# SignBuddy_Main_Board_Schematic.net
KiCad netlist of a schematic drawn in EAGLE
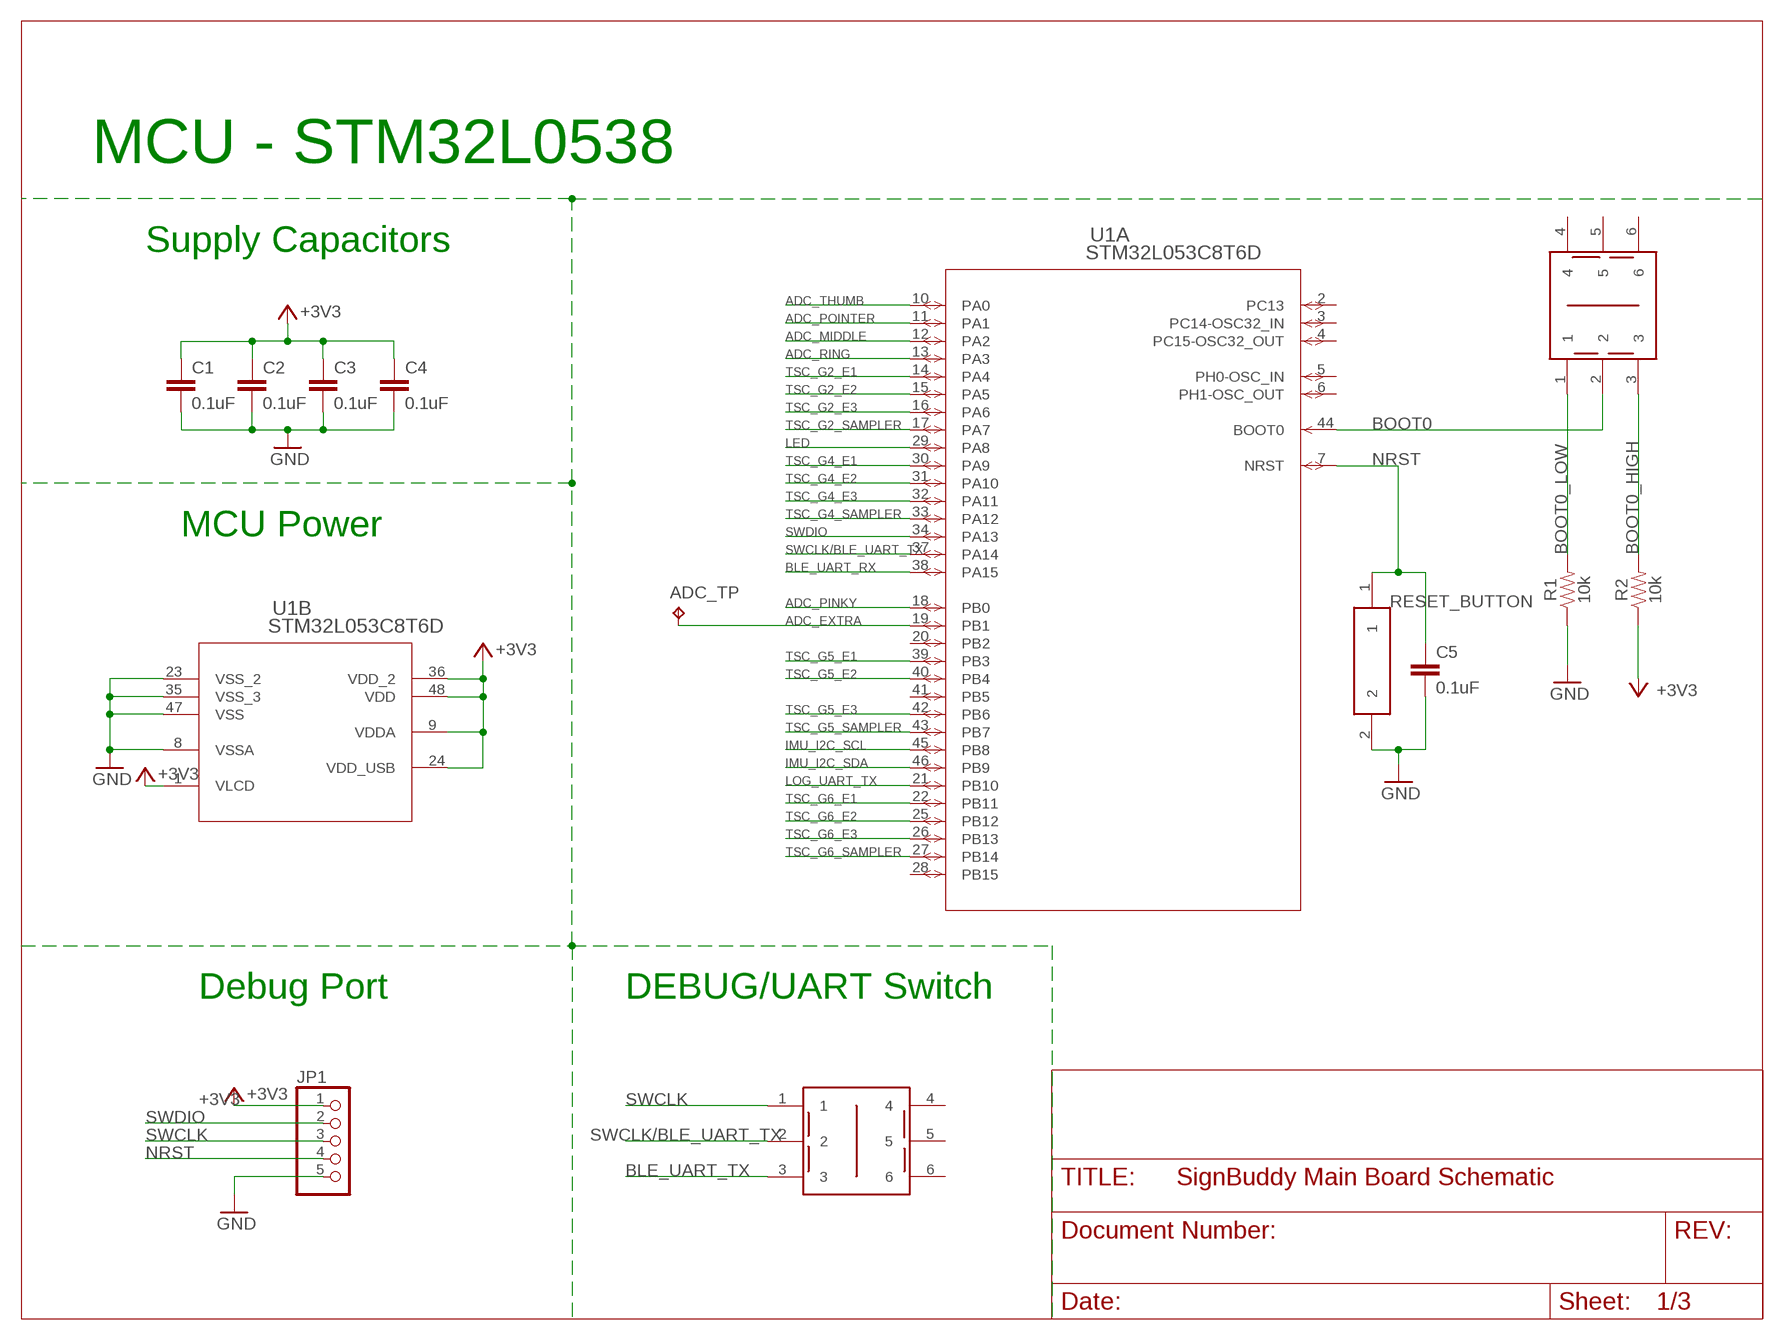
[diagram p0: schematic, sheet 1]
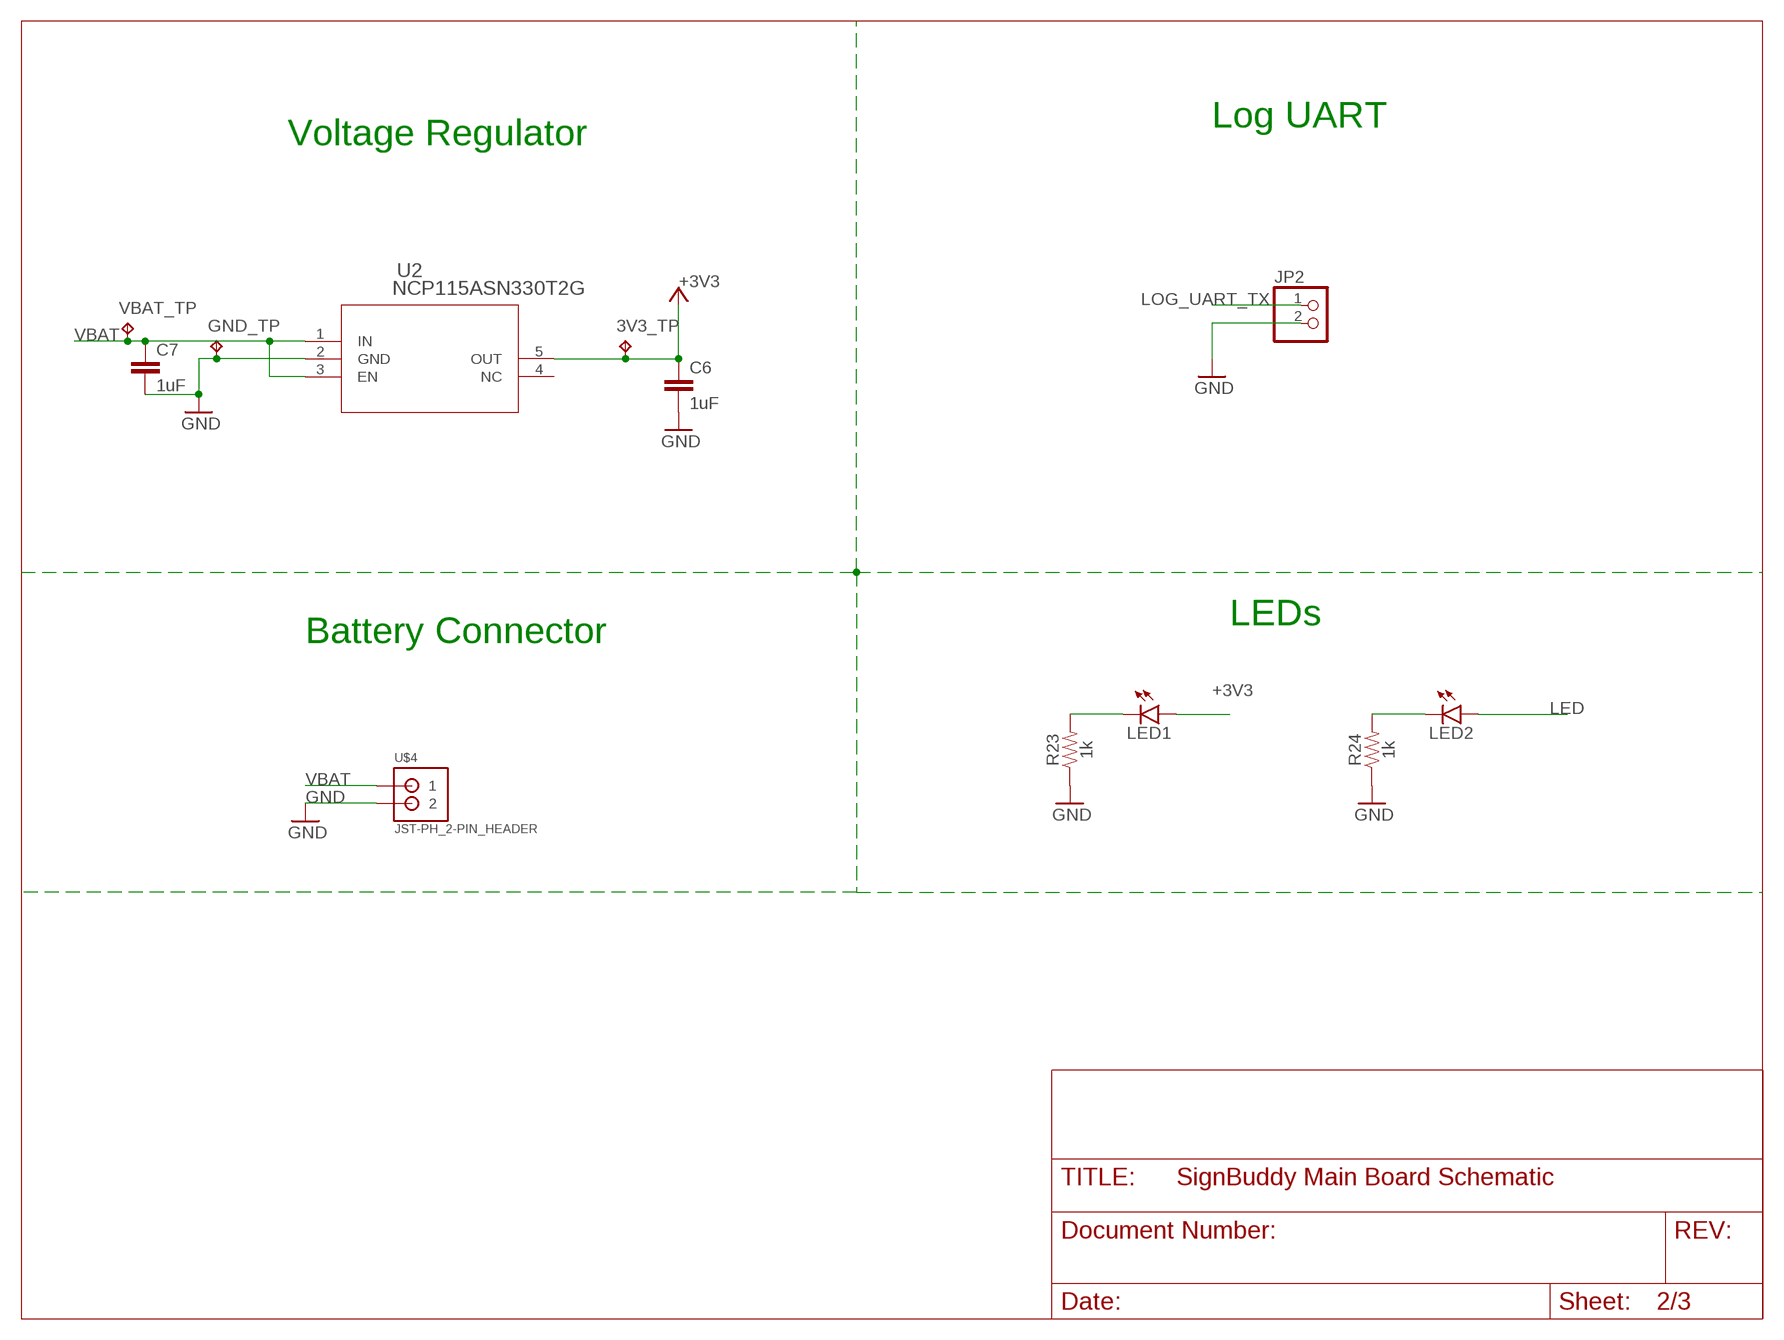
[diagram p1: schematic, sheet 2]
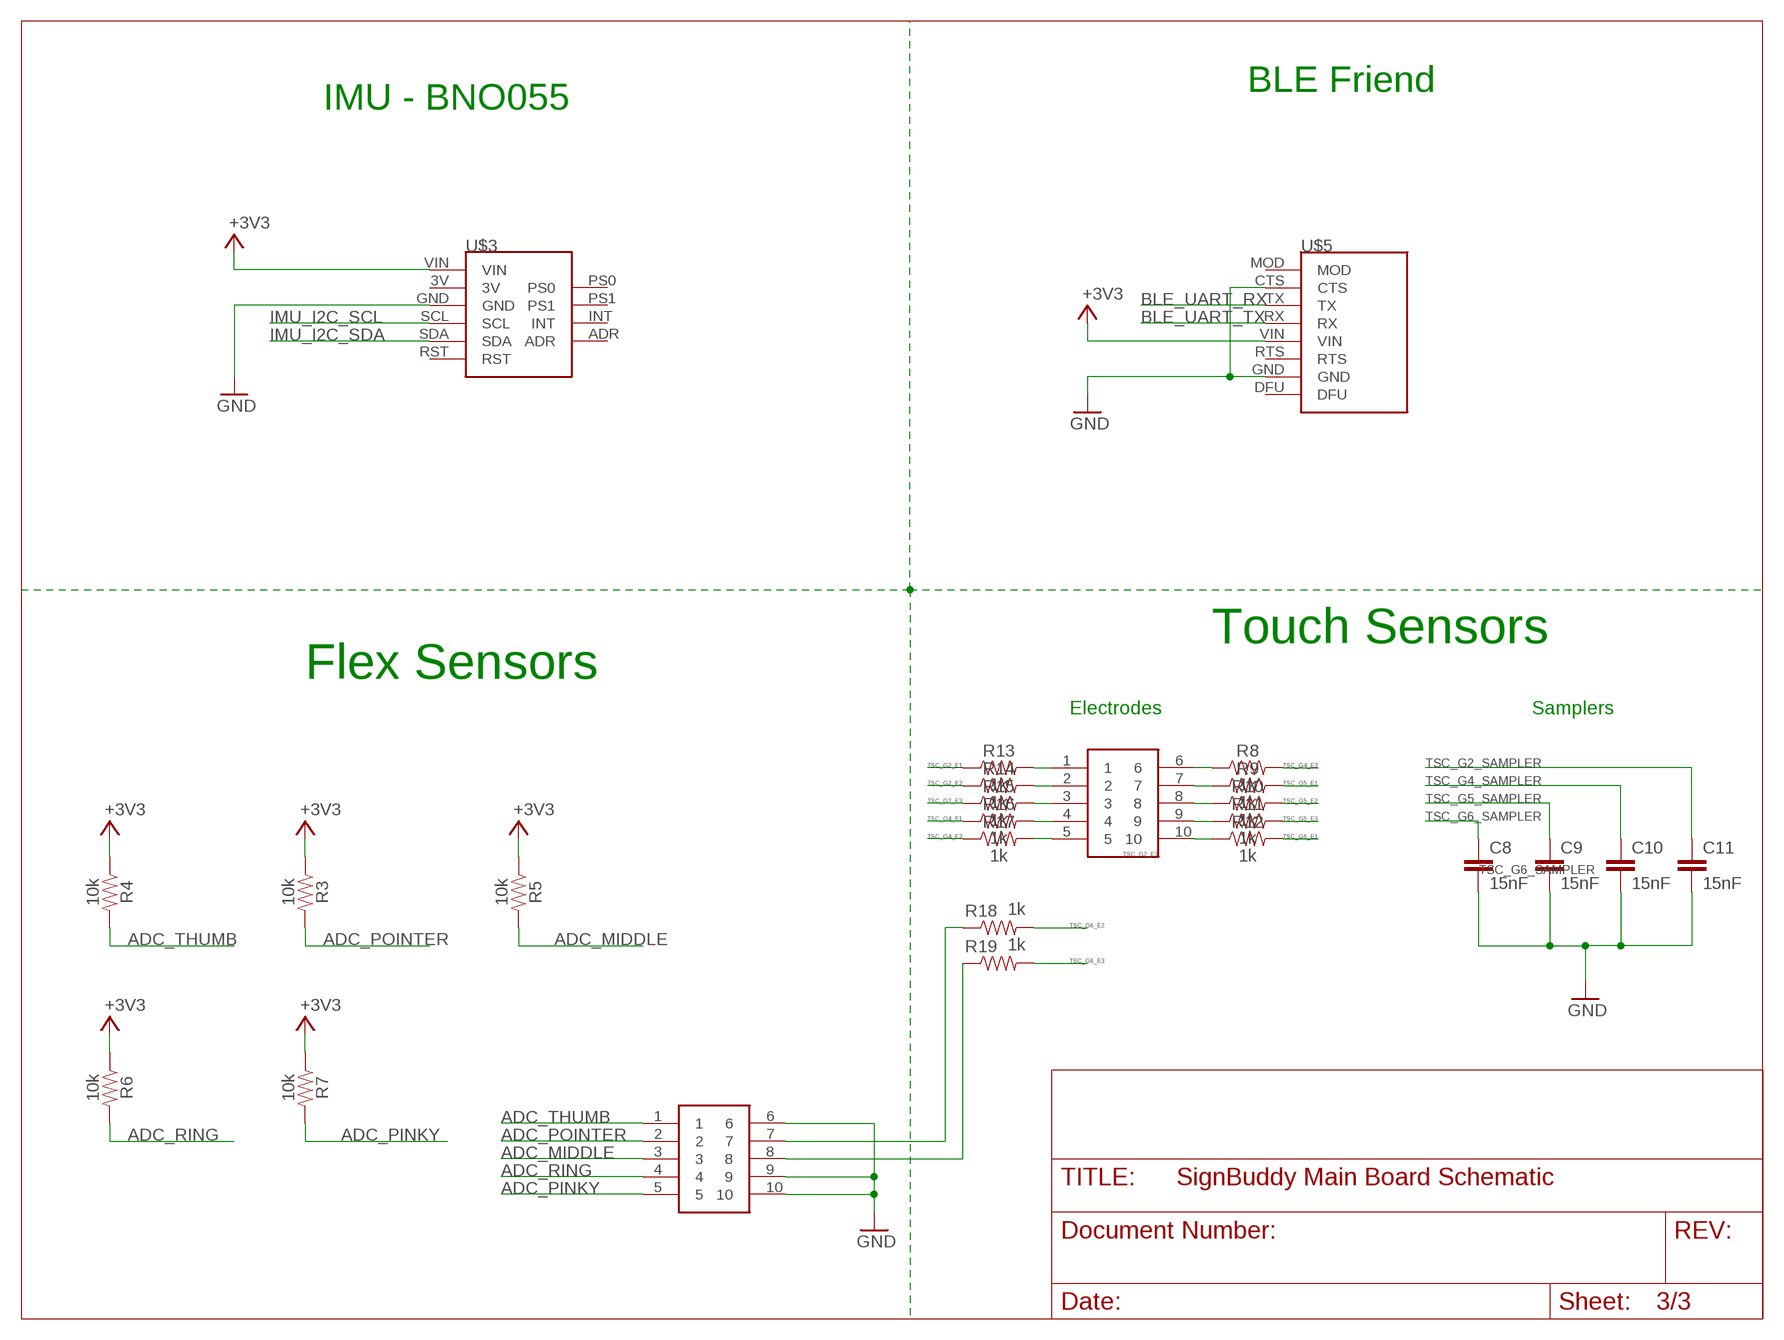
[diagram p2: schematic, sheet 3]

(export (version "E")
  (design (tool "Eeschema 10.0.6"))
  (components
    (comp (ref "ADC_TP")
      (value "TPB1,27")
      (footprint "eagle-import:B1,27")
      (libsource (lib "eagle-import") (part "TPB1,27"))
    )
    (comp (ref "C1")
      (value "0.1uF")
      (footprint "eagle-import:0603")
      (libsource (lib "eagle-import") (part "10UF-0603-6.3V-20%"))
    )
    (comp (ref "C2")
      (value "0.1uF")
      (footprint "eagle-import:0603")
      (libsource (lib "eagle-import") (part "10UF-0603-6.3V-20%"))
    )
    (comp (ref "C3")
      (value "0.1uF")
      (footprint "eagle-import:0603")
      (libsource (lib "eagle-import") (part "10UF-0603-6.3V-20%"))
    )
    (comp (ref "C4")
      (value "0.1uF")
      (footprint "eagle-import:0603")
      (libsource (lib "eagle-import") (part "10UF-0603-6.3V-20%"))
    )
    (comp (ref "C5")
      (value "0.1uF")
      (footprint "eagle-import:0603")
      (libsource (lib "eagle-import") (part "10UF-0603-6.3V-20%"))
    )
    (comp (ref "JP1")
      (value "PINHD-1X5")
      (footprint "eagle-import:1X05")
      (libsource (lib "eagle-import") (part "PINHD-1X5"))
    )
    (comp (ref "R1")
      (value "10k")
      (footprint "eagle-import:0603")
      (libsource (lib "eagle-import") (part "1.8KOHM-0603-1/10W-1%"))
    )
    (comp (ref "R2")
      (value "10k")
      (footprint "eagle-import:0603")
      (libsource (lib "eagle-import") (part "1.8KOHM-0603-1/10W-1%"))
    )
    (comp (ref "RESET_BUTTON")
      (value "PUSH_BUTTON")
      (footprint "eagle-import:PUSH_BUTTON")
      (libsource (lib "eagle-import") (part "PUSH_BUTTON"))
    )
    (comp (ref "U$1")
      (value "SLIDE_SWITCH")
      (footprint "eagle-import:SLIDE_SWITCH")
      (libsource (lib "eagle-import") (part "SLIDE_SWITCH"))
    )
    (comp (ref "U$2")
      (value "SLIDE_SWITCH")
      (footprint "eagle-import:SLIDE_SWITCH")
      (libsource (lib "eagle-import") (part "SLIDE_SWITCH"))
    )
    (comp (ref "U1")
      (value "STM32L053C8T6D")
      (footprint "eagle-import:LQFP48-7X7MM")
      (fields (field (name "COPYRIGHT") "Copyright (C) 2022 Ultra Librarian. All rights reserved."))
      (libsource (lib "eagle-import") (part "STM32L053C8T6D"))
    )
    (comp (ref "3V3_TP")
      (value "TPB1,27")
      (footprint "eagle-import:B1,27")
      (libsource (lib "eagle-import") (part "TPB1,27"))
    )
    (comp (ref "C6")
      (value "1uF")
      (footprint "eagle-import:0603")
      (libsource (lib "eagle-import") (part "10UF-0603-6.3V-20%"))
    )
    (comp (ref "C7")
      (value "1uF")
      (footprint "eagle-import:0603")
      (libsource (lib "eagle-import") (part "10UF-0603-6.3V-20%"))
    )
    (comp (ref "GND_TP")
      (value "TPB1,27")
      (footprint "eagle-import:B1,27")
      (libsource (lib "eagle-import") (part "TPB1,27"))
    )
    (comp (ref "JP2")
      (value "PINHD-1X2")
      (footprint "eagle-import:1X02")
      (libsource (lib "eagle-import") (part "PINHD-1X2"))
    )
    (comp (ref "LED1")
      (value "LEDCHIP-LED0603")
      (footprint "eagle-import:CHIP-LED0603")
      (libsource (lib "eagle-import") (part "LEDCHIP-LED0603"))
    )
    (comp (ref "LED2")
      (value "LEDCHIP-LED0603")
      (footprint "eagle-import:CHIP-LED0603")
      (libsource (lib "eagle-import") (part "LEDCHIP-LED0603"))
    )
    (comp (ref "R23")
      (value "1k")
      (footprint "eagle-import:0603")
      (libsource (lib "eagle-import") (part "1.5KOHM-0603-1/10W-1%"))
    )
    (comp (ref "R24")
      (value "1k")
      (footprint "eagle-import:0603")
      (libsource (lib "eagle-import") (part "1.5KOHM-0603-1/10W-1%"))
    )
    (comp (ref "U$4")
      (value "JST-PH_2-PIN_HEADER")
      (footprint "eagle-import:JST_B2B-PH_HEADER")
      (libsource (lib "eagle-import") (part "JST-PH_2-PIN_HEADER"))
    )
    (comp (ref "U2")
      (value "NCP115ASN330T2G")
      (footprint "eagle-import:TSOP-5-483-N_ONS")
      (fields (field (name "COPYRIGHT") "Copyright (C) 2022 Ultra Librarian. All rights reserved."))
      (libsource (lib "eagle-import") (part "NCP115ASN330T2G"))
    )
    (comp (ref "VBAT_TP")
      (value "TPB1,27")
      (footprint "eagle-import:B1,27")
      (libsource (lib "eagle-import") (part "TPB1,27"))
    )
    (comp (ref "C8")
      (value "15nF")
      (footprint "eagle-import:0603")
      (libsource (lib "eagle-import") (part "10UF-0603-6.3V-20%"))
    )
    (comp (ref "C9")
      (value "15nF")
      (footprint "eagle-import:0603")
      (libsource (lib "eagle-import") (part "10UF-0603-6.3V-20%"))
    )
    (comp (ref "C10")
      (value "15nF")
      (footprint "eagle-import:0603")
      (libsource (lib "eagle-import") (part "10UF-0603-6.3V-20%"))
    )
    (comp (ref "C11")
      (value "15nF")
      (footprint "eagle-import:0603")
      (libsource (lib "eagle-import") (part "10UF-0603-6.3V-20%"))
    )
    (comp (ref "R3")
      (value "10k")
      (footprint "eagle-import:0603")
      (libsource (lib "eagle-import") (part "10KOHM-0603-1/10W-1%"))
    )
    (comp (ref "R4")
      (value "10k")
      (footprint "eagle-import:0603")
      (libsource (lib "eagle-import") (part "10KOHM-0603-1/10W-1%"))
    )
    (comp (ref "R5")
      (value "10k")
      (footprint "eagle-import:0603")
      (libsource (lib "eagle-import") (part "10KOHM-0603-1/10W-1%"))
    )
    (comp (ref "R6")
      (value "10k")
      (footprint "eagle-import:0603")
      (libsource (lib "eagle-import") (part "10KOHM-0603-1/10W-1%"))
    )
    (comp (ref "R7")
      (value "10k")
      (footprint "eagle-import:0603")
      (libsource (lib "eagle-import") (part "10KOHM-0603-1/10W-1%"))
    )
    (comp (ref "R8")
      (value "1k")
      (footprint "eagle-import:0603")
      (libsource (lib "eagle-import") (part "10KOHM-0603-1/10W-1%"))
    )
    (comp (ref "R9")
      (value "1k")
      (footprint "eagle-import:0603")
      (libsource (lib "eagle-import") (part "10KOHM-0603-1/10W-1%"))
    )
    (comp (ref "R10")
      (value "1k")
      (footprint "eagle-import:0603")
      (libsource (lib "eagle-import") (part "10KOHM-0603-1/10W-1%"))
    )
    (comp (ref "R11")
      (value "1k")
      (footprint "eagle-import:0603")
      (libsource (lib "eagle-import") (part "10KOHM-0603-1/10W-1%"))
    )
    (comp (ref "R12")
      (value "1k")
      (footprint "eagle-import:0603")
      (libsource (lib "eagle-import") (part "10KOHM-0603-1/10W-1%"))
    )
    (comp (ref "R13")
      (value "1k")
      (footprint "eagle-import:0603")
      (libsource (lib "eagle-import") (part "10KOHM-0603-1/10W-1%"))
    )
    (comp (ref "R14")
      (value "1k")
      (footprint "eagle-import:0603")
      (libsource (lib "eagle-import") (part "10KOHM-0603-1/10W-1%"))
    )
    (comp (ref "R15")
      (value "1k")
      (footprint "eagle-import:0603")
      (libsource (lib "eagle-import") (part "10KOHM-0603-1/10W-1%"))
    )
    (comp (ref "R16")
      (value "1k")
      (footprint "eagle-import:0603")
      (libsource (lib "eagle-import") (part "10KOHM-0603-1/10W-1%"))
    )
    (comp (ref "R17")
      (value "1k")
      (footprint "eagle-import:0603")
      (libsource (lib "eagle-import") (part "10KOHM-0603-1/10W-1%"))
    )
    (comp (ref "R18")
      (value "1k")
      (footprint "eagle-import:0603")
      (libsource (lib "eagle-import") (part "10KOHM-0603-1/10W-1%"))
    )
    (comp (ref "R19")
      (value "1k")
      (footprint "eagle-import:0603")
      (libsource (lib "eagle-import") (part "10KOHM-0603-1/10W-1%"))
    )
    (comp (ref "U$3")
      (value "BNO055-ADAFRUIT")
      (footprint "eagle-import:BNO055-ADAFRUIT")
      (libsource (lib "eagle-import") (part "BNO055-ADAFRUIT"))
    )
    (comp (ref "U$5")
      (value "BLE_FRIEND")
      (footprint "eagle-import:BLE_FRIEND")
      (libsource (lib "eagle-import") (part "BLE_FRIEND"))
    )
    (comp (ref "U$6")
      (value "10PIN_CONNECTOR")
      (footprint "eagle-import:10PIN_CONNECTOR")
      (libsource (lib "eagle-import") (part "10PIN_CONNECTOR"))
    )
    (comp (ref "U$7")
      (value "10PIN_CONNECTOR")
      (footprint "eagle-import:10PIN_CONNECTOR")
      (libsource (lib "eagle-import") (part "10PIN_CONNECTOR"))
    )
  )
  (nets
    (net (code "1") (name "+3V3") (class "Default")
      (node (ref "3V3_TP") (pin "TP") (pinfunction "TP_TP") (pintype "input"))
      (node (ref "C1") (pin "1") (pinfunction "1_1") (pintype "passive"))
      (node (ref "C2") (pin "1") (pinfunction "1_1") (pintype "passive"))
      (node (ref "C3") (pin "1") (pinfunction "1_1") (pintype "passive"))
      (node (ref "C4") (pin "1") (pinfunction "1_1") (pintype "passive"))
      (node (ref "C6") (pin "1") (pinfunction "1_1") (pintype "passive"))
      (node (ref "JP1") (pin "1") (pinfunction "1_1") (pintype "passive"))
      (node (ref "LED1") (pin "A") (pinfunction "A_A") (pintype "passive"))
      (node (ref "R2") (pin "1") (pinfunction "1_1") (pintype "passive"))
      (node (ref "R3") (pin "1") (pinfunction "1_1") (pintype "passive"))
      (node (ref "R4") (pin "1") (pinfunction "1_1") (pintype "passive"))
      (node (ref "R5") (pin "1") (pinfunction "1_1") (pintype "passive"))
      (node (ref "R6") (pin "1") (pinfunction "1_1") (pintype "passive"))
      (node (ref "R7") (pin "1") (pinfunction "1_1") (pintype "passive"))
      (node (ref "U$3") (pin "VIN") (pinfunction "VIN_VIN") (pintype "bidirectional"))
      (node (ref "U$5") (pin "VIN") (pinfunction "VIN_VIN") (pintype "bidirectional"))
      (node (ref "U1") (pin "1") (pinfunction "VLCD_1") (pintype "power_in"))
      (node (ref "U1") (pin "24") (pinfunction "VDD_USB_24") (pintype "power_in"))
      (node (ref "U1") (pin "36") (pinfunction "VDD_2_36") (pintype "power_in"))
      (node (ref "U1") (pin "48") (pinfunction "VDD_48") (pintype "power_in"))
      (node (ref "U1") (pin "9") (pinfunction "VDDA_9") (pintype "power_in"))
      (node (ref "U2") (pin "5") (pinfunction "OUT_5") (pintype "output"))
    )
    (net (code "2") (name "ADC_EXTRA") (class "Default")
      (node (ref "ADC_TP") (pin "TP") (pinfunction "TP_TP") (pintype "input"))
      (node (ref "U1") (pin "19") (pinfunction "PB1_19") (pintype "bidirectional"))
    )
    (net (code "3") (name "ADC_MIDDLE") (class "Default")
      (node (ref "R5") (pin "2") (pinfunction "2_2") (pintype "passive"))
      (node (ref "U$7") (pin "3") (pinfunction "3_3") (pintype "bidirectional"))
      (node (ref "U1") (pin "12") (pinfunction "PA2_12") (pintype "bidirectional"))
    )
    (net (code "4") (name "ADC_PINKY") (class "Default")
      (node (ref "R7") (pin "2") (pinfunction "2_2") (pintype "passive"))
      (node (ref "U$7") (pin "5") (pinfunction "5_5") (pintype "bidirectional"))
      (node (ref "U1") (pin "18") (pinfunction "PB0_18") (pintype "bidirectional"))
    )
    (net (code "5") (name "ADC_POINTER") (class "Default")
      (node (ref "R3") (pin "2") (pinfunction "2_2") (pintype "passive"))
      (node (ref "U$7") (pin "2") (pinfunction "2_2") (pintype "bidirectional"))
      (node (ref "U1") (pin "11") (pinfunction "PA1_11") (pintype "bidirectional"))
    )
    (net (code "6") (name "ADC_RING") (class "Default")
      (node (ref "R6") (pin "2") (pinfunction "2_2") (pintype "passive"))
      (node (ref "U$7") (pin "4") (pinfunction "4_4") (pintype "bidirectional"))
      (node (ref "U1") (pin "13") (pinfunction "PA3_13") (pintype "bidirectional"))
    )
    (net (code "7") (name "ADC_THUMB") (class "Default")
      (node (ref "R4") (pin "2") (pinfunction "2_2") (pintype "passive"))
      (node (ref "U$7") (pin "1") (pinfunction "1_1") (pintype "bidirectional"))
      (node (ref "U1") (pin "10") (pinfunction "PA0_10") (pintype "bidirectional"))
    )
    (net (code "8") (name "BLE_UART_RX") (class "Default")
      (node (ref "U$5") (pin "TX") (pinfunction "TX_TX") (pintype "bidirectional"))
      (node (ref "U1") (pin "38") (pinfunction "PA15_38") (pintype "bidirectional"))
    )
    (net (code "9") (name "BLE_UART_TX") (class "Default")
      (node (ref "U$2") (pin "3") (pinfunction "3_3") (pintype "bidirectional"))
      (node (ref "U$5") (pin "RX") (pinfunction "RX_RX") (pintype "bidirectional"))
    )
    (net (code "10") (name "BOOT0") (class "Default")
      (node (ref "U$1") (pin "2") (pinfunction "2_2") (pintype "bidirectional"))
      (node (ref "U1") (pin "44") (pinfunction "BOOT0_44") (pintype "input"))
    )
    (net (code "11") (name "BOOT0_HIGH") (class "Default")
      (node (ref "R2") (pin "2") (pinfunction "2_2") (pintype "passive"))
      (node (ref "U$1") (pin "3") (pinfunction "3_3") (pintype "bidirectional"))
    )
    (net (code "12") (name "BOOT0_LOW") (class "Default")
      (node (ref "R1") (pin "2") (pinfunction "2_2") (pintype "passive"))
      (node (ref "U$1") (pin "1") (pinfunction "1_1") (pintype "bidirectional"))
    )
    (net (code "13") (name "GND") (class "Default")
      (node (ref "C1") (pin "2") (pinfunction "2_2") (pintype "passive"))
      (node (ref "C10") (pin "2") (pinfunction "2_2") (pintype "passive"))
      (node (ref "C11") (pin "2") (pinfunction "2_2") (pintype "passive"))
      (node (ref "C2") (pin "2") (pinfunction "2_2") (pintype "passive"))
      (node (ref "C3") (pin "2") (pinfunction "2_2") (pintype "passive"))
      (node (ref "C4") (pin "2") (pinfunction "2_2") (pintype "passive"))
      (node (ref "C5") (pin "2") (pinfunction "2_2") (pintype "passive"))
      (node (ref "C6") (pin "2") (pinfunction "2_2") (pintype "passive"))
      (node (ref "C7") (pin "2") (pinfunction "2_2") (pintype "passive"))
      (node (ref "C8") (pin "2") (pinfunction "2_2") (pintype "passive"))
      (node (ref "C9") (pin "2") (pinfunction "2_2") (pintype "passive"))
      (node (ref "GND_TP") (pin "TP") (pinfunction "TP_TP") (pintype "input"))
      (node (ref "JP1") (pin "5") (pinfunction "5_5") (pintype "passive"))
      (node (ref "JP2") (pin "2") (pinfunction "2_2") (pintype "passive"))
      (node (ref "R1") (pin "1") (pinfunction "1_1") (pintype "passive"))
      (node (ref "R23") (pin "1") (pinfunction "1_1") (pintype "passive"))
      (node (ref "R24") (pin "1") (pinfunction "1_1") (pintype "passive"))
      (node (ref "RESET_BUTTON") (pin "2") (pinfunction "2_2") (pintype "bidirectional"))
      (node (ref "U$3") (pin "GND") (pinfunction "GND_GND") (pintype "bidirectional"))
      (node (ref "U$4") (pin "P2") (pinfunction "2_P2") (pintype "bidirectional"))
      (node (ref "U$5") (pin "CTS") (pinfunction "CTS_CTS") (pintype "bidirectional"))
      (node (ref "U$5") (pin "GND") (pinfunction "GND_GND") (pintype "bidirectional"))
      (node (ref "U$7") (pin "10") (pinfunction "10_10") (pintype "bidirectional"))
      (node (ref "U$7") (pin "6") (pinfunction "6_6") (pintype "bidirectional"))
      (node (ref "U$7") (pin "9") (pinfunction "9_9") (pintype "bidirectional"))
      (node (ref "U1") (pin "23") (pinfunction "VSS_2_23") (pintype "power_in"))
      (node (ref "U1") (pin "35") (pinfunction "VSS_3_35") (pintype "power_in"))
      (node (ref "U1") (pin "47") (pinfunction "VSS_47") (pintype "power_in"))
      (node (ref "U1") (pin "8") (pinfunction "VSSA_8") (pintype "power_in"))
      (node (ref "U2") (pin "2") (pinfunction "GND_2") (pintype "passive"))
    )
    (net (code "14") (name "IMU_I2C_SCL") (class "Default")
      (node (ref "U$3") (pin "SCL") (pinfunction "SCL_SCL") (pintype "bidirectional"))
      (node (ref "U1") (pin "45") (pinfunction "PB8_45") (pintype "bidirectional"))
    )
    (net (code "15") (name "IMU_I2C_SDA") (class "Default")
      (node (ref "U$3") (pin "SDA") (pinfunction "SDA_SDA") (pintype "bidirectional"))
      (node (ref "U1") (pin "46") (pinfunction "PB9_46") (pintype "bidirectional"))
    )
    (net (code "16") (name "LED") (class "Default")
      (node (ref "LED2") (pin "A") (pinfunction "A_A") (pintype "passive"))
      (node (ref "U1") (pin "29") (pinfunction "PA8_29") (pintype "bidirectional"))
    )
    (net (code "17") (name "LOG_UART_TX") (class "Default")
      (node (ref "JP2") (pin "1") (pinfunction "1_1") (pintype "passive"))
      (node (ref "U1") (pin "21") (pinfunction "PB10_21") (pintype "bidirectional"))
    )
    (net (code "18") (name "NRST") (class "Default")
      (node (ref "C5") (pin "1") (pinfunction "1_1") (pintype "passive"))
      (node (ref "JP1") (pin "4") (pinfunction "4_4") (pintype "passive"))
      (node (ref "RESET_BUTTON") (pin "1") (pinfunction "1_1") (pintype "bidirectional"))
      (node (ref "U1") (pin "7") (pinfunction "NRST_7") (pintype "bidirectional"))
    )
    (net (code "19") (name "Net-(LED1-PadC)") (class "Default")
      (node (ref "LED1") (pin "C") (pinfunction "C_C") (pintype "passive"))
      (node (ref "R23") (pin "2") (pinfunction "2_2") (pintype "passive"))
    )
    (net (code "20") (name "Net-(LED2-PadC)") (class "Default")
      (node (ref "LED2") (pin "C") (pinfunction "C_C") (pintype "passive"))
      (node (ref "R24") (pin "2") (pinfunction "2_2") (pintype "passive"))
    )
    (net (code "21") (name "Net-(R8-Pad1)") (class "Default")
      (node (ref "R8") (pin "1") (pinfunction "1_1") (pintype "passive"))
      (node (ref "U$6") (pin "6") (pinfunction "6_6") (pintype "bidirectional"))
    )
    (net (code "22") (name "Net-(R9-Pad1)") (class "Default")
      (node (ref "R9") (pin "1") (pinfunction "1_1") (pintype "passive"))
      (node (ref "U$6") (pin "7") (pinfunction "7_7") (pintype "bidirectional"))
    )
    (net (code "23") (name "Net-(R10-Pad1)") (class "Default")
      (node (ref "R10") (pin "1") (pinfunction "1_1") (pintype "passive"))
      (node (ref "U$6") (pin "8") (pinfunction "8_8") (pintype "bidirectional"))
    )
    (net (code "24") (name "Net-(R11-Pad1)") (class "Default")
      (node (ref "R11") (pin "1") (pinfunction "1_1") (pintype "passive"))
      (node (ref "U$6") (pin "9") (pinfunction "9_9") (pintype "bidirectional"))
    )
    (net (code "25") (name "Net-(R12-Pad1)") (class "Default")
      (node (ref "R12") (pin "1") (pinfunction "1_1") (pintype "passive"))
      (node (ref "U$6") (pin "10") (pinfunction "10_10") (pintype "bidirectional"))
    )
    (net (code "26") (name "Net-(R13-Pad2)") (class "Default")
      (node (ref "R13") (pin "2") (pinfunction "2_2") (pintype "passive"))
      (node (ref "U$6") (pin "1") (pinfunction "1_1") (pintype "bidirectional"))
    )
    (net (code "27") (name "Net-(R14-Pad2)") (class "Default")
      (node (ref "R14") (pin "2") (pinfunction "2_2") (pintype "passive"))
      (node (ref "U$6") (pin "2") (pinfunction "2_2") (pintype "bidirectional"))
    )
    (net (code "28") (name "Net-(R15-Pad2)") (class "Default")
      (node (ref "R15") (pin "2") (pinfunction "2_2") (pintype "passive"))
      (node (ref "U$6") (pin "3") (pinfunction "3_3") (pintype "bidirectional"))
    )
    (net (code "29") (name "Net-(R16-Pad2)") (class "Default")
      (node (ref "R16") (pin "2") (pinfunction "2_2") (pintype "passive"))
      (node (ref "U$6") (pin "4") (pinfunction "4_4") (pintype "bidirectional"))
    )
    (net (code "30") (name "Net-(R17-Pad2)") (class "Default")
      (node (ref "R17") (pin "2") (pinfunction "2_2") (pintype "passive"))
      (node (ref "U$6") (pin "5") (pinfunction "5_5") (pintype "bidirectional"))
    )
    (net (code "31") (name "Net-(R18-Pad1)") (class "Default")
      (node (ref "R18") (pin "1") (pinfunction "1_1") (pintype "passive"))
      (node (ref "U$7") (pin "7") (pinfunction "7_7") (pintype "bidirectional"))
    )
    (net (code "32") (name "Net-(R19-Pad1)") (class "Default")
      (node (ref "R19") (pin "1") (pinfunction "1_1") (pintype "passive"))
      (node (ref "U$7") (pin "8") (pinfunction "8_8") (pintype "bidirectional"))
    )
    (net (code "33") (name "SWCLK") (class "Default")
      (node (ref "JP1") (pin "3") (pinfunction "3_3") (pintype "passive"))
      (node (ref "U$2") (pin "1") (pinfunction "1_1") (pintype "bidirectional"))
    )
    (net (code "34") (name "SWCLK{slash}BLE_UART_TX") (class "Default")
      (node (ref "U$2") (pin "2") (pinfunction "2_2") (pintype "bidirectional"))
      (node (ref "U1") (pin "37") (pinfunction "PA14_37") (pintype "bidirectional"))
    )
    (net (code "35") (name "SWDIO") (class "Default")
      (node (ref "JP1") (pin "2") (pinfunction "2_2") (pintype "passive"))
      (node (ref "U1") (pin "34") (pinfunction "PA13_34") (pintype "bidirectional"))
    )
    (net (code "36") (name "TSC_G2_E1") (class "Default")
      (node (ref "R13") (pin "1") (pinfunction "1_1") (pintype "passive"))
      (node (ref "U1") (pin "14") (pinfunction "PA4_14") (pintype "bidirectional"))
    )
    (net (code "37") (name "TSC_G2_E2") (class "Default")
      (node (ref "R14") (pin "1") (pinfunction "1_1") (pintype "passive"))
      (node (ref "U1") (pin "15") (pinfunction "PA5_15") (pintype "bidirectional"))
    )
    (net (code "38") (name "TSC_G2_E3") (class "Default")
      (node (ref "R15") (pin "1") (pinfunction "1_1") (pintype "passive"))
      (node (ref "U1") (pin "16") (pinfunction "PA6_16") (pintype "bidirectional"))
    )
    (net (code "39") (name "TSC_G2_SAMPLER") (class "Default")
      (node (ref "C11") (pin "1") (pinfunction "1_1") (pintype "passive"))
      (node (ref "U1") (pin "17") (pinfunction "PA7_17") (pintype "bidirectional"))
    )
    (net (code "40") (name "TSC_G4_E1") (class "Default")
      (node (ref "R16") (pin "1") (pinfunction "1_1") (pintype "passive"))
      (node (ref "U1") (pin "30") (pinfunction "PA9_30") (pintype "bidirectional"))
    )
    (net (code "41") (name "TSC_G4_E2") (class "Default")
      (node (ref "R17") (pin "1") (pinfunction "1_1") (pintype "passive"))
      (node (ref "U1") (pin "31") (pinfunction "PA10_31") (pintype "bidirectional"))
    )
    (net (code "42") (name "TSC_G4_E3") (class "Default")
      (node (ref "R8") (pin "2") (pinfunction "2_2") (pintype "passive"))
      (node (ref "U1") (pin "32") (pinfunction "PA11_32") (pintype "bidirectional"))
    )
    (net (code "43") (name "TSC_G4_SAMPLER") (class "Default")
      (node (ref "C10") (pin "1") (pinfunction "1_1") (pintype "passive"))
      (node (ref "U1") (pin "33") (pinfunction "PA12_33") (pintype "bidirectional"))
    )
    (net (code "44") (name "TSC_G5_E1") (class "Default")
      (node (ref "R9") (pin "2") (pinfunction "2_2") (pintype "passive"))
      (node (ref "U1") (pin "39") (pinfunction "PB3_39") (pintype "bidirectional"))
    )
    (net (code "45") (name "TSC_G5_E2") (class "Default")
      (node (ref "R10") (pin "2") (pinfunction "2_2") (pintype "passive"))
      (node (ref "U1") (pin "40") (pinfunction "PB4_40") (pintype "bidirectional"))
    )
    (net (code "46") (name "TSC_G5_E3") (class "Default")
      (node (ref "R11") (pin "2") (pinfunction "2_2") (pintype "passive"))
      (node (ref "U1") (pin "42") (pinfunction "PB6_42") (pintype "bidirectional"))
    )
    (net (code "47") (name "TSC_G5_SAMPLER") (class "Default")
      (node (ref "C9") (pin "1") (pinfunction "1_1") (pintype "passive"))
      (node (ref "U1") (pin "43") (pinfunction "PB7_43") (pintype "bidirectional"))
    )
    (net (code "48") (name "TSC_G6_E1") (class "Default")
      (node (ref "R12") (pin "2") (pinfunction "2_2") (pintype "passive"))
      (node (ref "U1") (pin "22") (pinfunction "PB11_22") (pintype "bidirectional"))
    )
    (net (code "49") (name "TSC_G6_E2") (class "Default")
      (node (ref "R18") (pin "2") (pinfunction "2_2") (pintype "passive"))
      (node (ref "U1") (pin "25") (pinfunction "PB12_25") (pintype "bidirectional"))
    )
    (net (code "50") (name "TSC_G6_E3") (class "Default")
      (node (ref "R19") (pin "2") (pinfunction "2_2") (pintype "passive"))
      (node (ref "U1") (pin "26") (pinfunction "PB13_26") (pintype "bidirectional"))
    )
    (net (code "51") (name "TSC_G6_SAMPLER") (class "Default")
      (node (ref "C8") (pin "1") (pinfunction "1_1") (pintype "passive"))
      (node (ref "U1") (pin "27") (pinfunction "PB14_27") (pintype "bidirectional"))
    )
    (net (code "52") (name "VBAT") (class "Default")
      (node (ref "C7") (pin "1") (pinfunction "1_1") (pintype "passive"))
      (node (ref "U$4") (pin "P1") (pinfunction "1_P1") (pintype "bidirectional"))
      (node (ref "U2") (pin "1") (pinfunction "IN_1") (pintype "input"))
      (node (ref "U2") (pin "3") (pinfunction "EN_3") (pintype "passive"))
      (node (ref "VBAT_TP") (pin "TP") (pinfunction "TP_TP") (pintype "input"))
    )
    (net (code "53") (name "unconnected-(U$1-Pad4)") (class "Default")
      (node (ref "U$1") (pin "4") (pinfunction "4_4") (pintype "bidirectional"))
    )
    (net (code "54") (name "unconnected-(U$1-Pad5)") (class "Default")
      (node (ref "U$1") (pin "5") (pinfunction "5_5") (pintype "bidirectional"))
    )
    (net (code "55") (name "unconnected-(U$1-Pad6)") (class "Default")
      (node (ref "U$1") (pin "6") (pinfunction "6_6") (pintype "bidirectional"))
    )
    (net (code "56") (name "unconnected-(U$2-Pad4)") (class "Default")
      (node (ref "U$2") (pin "4") (pinfunction "4_4") (pintype "bidirectional"))
    )
    (net (code "57") (name "unconnected-(U$2-Pad5)") (class "Default")
      (node (ref "U$2") (pin "5") (pinfunction "5_5") (pintype "bidirectional"))
    )
    (net (code "58") (name "unconnected-(U$2-Pad6)") (class "Default")
      (node (ref "U$2") (pin "6") (pinfunction "6_6") (pintype "bidirectional"))
    )
    (net (code "59") (name "unconnected-(U$3-Pad3V)") (class "Default")
      (node (ref "U$3") (pin "3V") (pinfunction "3V_3V") (pintype "bidirectional"))
    )
    (net (code "60") (name "unconnected-(U$3-PadADR)") (class "Default")
      (node (ref "U$3") (pin "ADR") (pinfunction "ADR_ADR") (pintype "bidirectional"))
    )
    (net (code "61") (name "unconnected-(U$3-PadINT)") (class "Default")
      (node (ref "U$3") (pin "INT") (pinfunction "INT_INT") (pintype "bidirectional"))
    )
    (net (code "62") (name "unconnected-(U$3-PadPS0)") (class "Default")
      (node (ref "U$3") (pin "PS0") (pinfunction "PS0_PS0") (pintype "bidirectional"))
    )
    (net (code "63") (name "unconnected-(U$3-PadPS1)") (class "Default")
      (node (ref "U$3") (pin "PS1") (pinfunction "PS1_PS1") (pintype "bidirectional"))
    )
    (net (code "64") (name "unconnected-(U$3-PadRST)") (class "Default")
      (node (ref "U$3") (pin "RST") (pinfunction "RST_RST") (pintype "bidirectional"))
    )
    (net (code "65") (name "unconnected-(U$5-PadDFU)") (class "Default")
      (node (ref "U$5") (pin "DFU") (pinfunction "DFU_DFU") (pintype "bidirectional"))
    )
    (net (code "66") (name "unconnected-(U$5-PadMOD)") (class "Default")
      (node (ref "U$5") (pin "MOD") (pinfunction "MOD_MOD") (pintype "bidirectional"))
    )
    (net (code "67") (name "unconnected-(U$5-PadRTS)") (class "Default")
      (node (ref "U$5") (pin "RTS") (pinfunction "RTS_RTS") (pintype "bidirectional"))
    )
    (net (code "68") (name "unconnected-(U1A-PB2-Pad20)") (class "Default")
      (node (ref "U1") (pin "20") (pinfunction "PB2_20") (pintype "bidirectional"))
    )
    (net (code "69") (name "unconnected-(U1A-PB5-Pad41)") (class "Default")
      (node (ref "U1") (pin "41") (pinfunction "PB5_41") (pintype "bidirectional"))
    )
    (net (code "70") (name "unconnected-(U1A-PB15-Pad28)") (class "Default")
      (node (ref "U1") (pin "28") (pinfunction "PB15_28") (pintype "bidirectional"))
    )
    (net (code "71") (name "unconnected-(U1A-PC13-Pad2)") (class "Default")
      (node (ref "U1") (pin "2") (pinfunction "PC13_2") (pintype "bidirectional"))
    )
    (net (code "72") (name "unconnected-(U1A-PC14-OSC32_IN-Pad3)") (class "Default")
      (node (ref "U1") (pin "3") (pinfunction "PC14-OSC32_IN_3") (pintype "bidirectional"))
    )
    (net (code "73") (name "unconnected-(U1A-PC15-OSC32_OUT-Pad4)") (class "Default")
      (node (ref "U1") (pin "4") (pinfunction "PC15-OSC32_OUT_4") (pintype "bidirectional"))
    )
    (net (code "74") (name "unconnected-(U1A-PH0-OSC_IN-Pad5)") (class "Default")
      (node (ref "U1") (pin "5") (pinfunction "PH0-OSC_IN_5") (pintype "bidirectional"))
    )
    (net (code "75") (name "unconnected-(U1A-PH1-OSC_OUT-Pad6)") (class "Default")
      (node (ref "U1") (pin "6") (pinfunction "PH1-OSC_OUT_6") (pintype "bidirectional"))
    )
    (net (code "76") (name "unconnected-(U2-NC-Pad4)") (class "Default")
      (node (ref "U2") (pin "4") (pinfunction "NC_4") (pintype "no_connect"))
    )
  )
)
